# riffleBoost.net
KiCad netlist of a schematic drawn in EAGLE
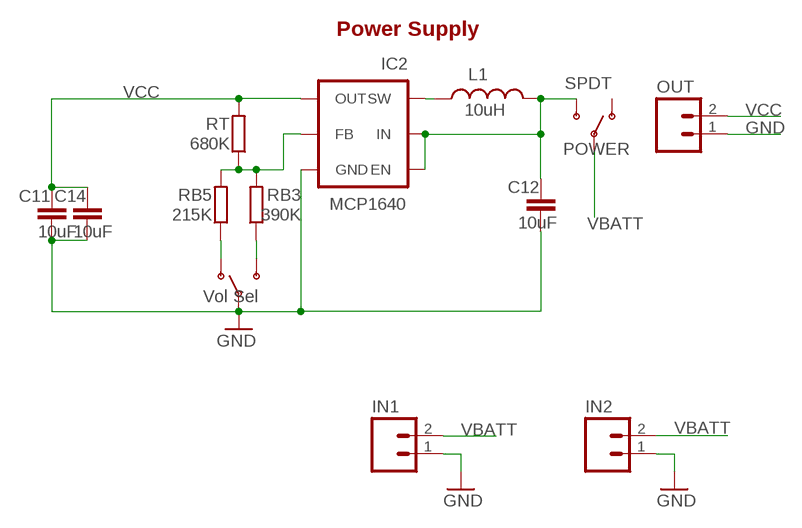
[diagram p0: schematic, sheet 1]

(export (version "E")
  (design (tool "Eeschema 10.0.6"))
  (components
    (comp (ref "C11")
      (value "10uF")
      (footprint "eagle-import:C0805")
      (libsource (lib "eagle-import") (part "C-EUC0805"))
    )
    (comp (ref "C12")
      (value "10uF")
      (footprint "eagle-import:C0805")
      (libsource (lib "eagle-import") (part "C-EUC0805"))
    )
    (comp (ref "C14")
      (value "10uF")
      (footprint "eagle-import:C0805")
      (libsource (lib "eagle-import") (part "C-EUC0805"))
    )
    (comp (ref "IC2")
      (value "MCP1640")
      (footprint "eagle-import:TSOT23-6")
      (libsource (lib "eagle-import") (part "MCP1640"))
    )
    (comp (ref "IN1")
      (value "M02PTH")
      (footprint "eagle-import:1X02")
      (libsource (lib "eagle-import") (part "M02PTH"))
    )
    (comp (ref "IN2")
      (value "M02-JST-2MM-SMT")
      (footprint "eagle-import:JST-2-SMD")
      (libsource (lib "eagle-import") (part "M02-JST-2MM-SMT"))
    )
    (comp (ref "L1")
      (value "10uH")
      (footprint "eagle-import:INDUCTOR_D30")
      (libsource (lib "eagle-import") (part "INDUCTOR_SMDD30"))
    )
    (comp (ref "OUT")
      (value "M021X02_NO_SILK")
      (footprint "eagle-import:1X02_NO_SILK")
      (libsource (lib "eagle-import") (part "M021X02_NO_SILK"))
    )
    (comp (ref "POWER")
      (value "SPDT")
      (footprint "eagle-import:SWITCH-SPDT-SMD")
      (libsource (lib "eagle-import") (part "SWITCH-SPSTSMD2"))
    )
    (comp (ref "RB3")
      (value "390K")
      (footprint "eagle-import:R0805")
      (libsource (lib "eagle-import") (part "R-EU_R0805"))
    )
    (comp (ref "RB5")
      (value "215K")
      (footprint "eagle-import:R0805")
      (libsource (lib "eagle-import") (part "R-EU_R0805"))
    )
    (comp (ref "RT")
      (value "680K")
      (footprint "eagle-import:R0805")
      (libsource (lib "eagle-import") (part "R-EU_R0805"))
    )
    (comp (ref "VOL1")
      (value "Vol Sel")
      (footprint "eagle-import:SWITCH-SPDT-SMD")
      (libsource (lib "eagle-import") (part "SWITCH-SPSTSMD2"))
    )
  )
  (nets
    (net (code "1") (name "/VBATT") (class "Default")
      (node (ref "IN1") (pin "2") (pinfunction "2_2") (pintype "passive"))
      (node (ref "IN2") (pin "2") (pinfunction "2_2") (pintype "passive"))
      (node (ref "POWER") (pin "2") (pinfunction "P_2") (pintype "passive"))
    )
    (net (code "2") (name "/VCC") (class "Default")
      (node (ref "C11") (pin "1") (pinfunction "1_1") (pintype "passive"))
      (node (ref "C14") (pin "1") (pinfunction "1_1") (pintype "passive"))
      (node (ref "IC2") (pin "5") (pinfunction "OUT_5") (pintype "passive"))
      (node (ref "OUT") (pin "2") (pinfunction "2_2") (pintype "passive"))
      (node (ref "RT") (pin "2") (pinfunction "2_2") (pintype "passive"))
    )
    (net (code "3") (name "GND") (class "Default")
      (node (ref "C11") (pin "2") (pinfunction "2_2") (pintype "passive"))
      (node (ref "C12") (pin "2") (pinfunction "2_2") (pintype "passive"))
      (node (ref "C14") (pin "2") (pinfunction "2_2") (pintype "passive"))
      (node (ref "IC2") (pin "2") (pinfunction "GND_2") (pintype "input"))
      (node (ref "IN1") (pin "1") (pinfunction "1_1") (pintype "passive"))
      (node (ref "IN2") (pin "1") (pinfunction "1_1") (pintype "passive"))
      (node (ref "OUT") (pin "1") (pinfunction "1_1") (pintype "passive"))
      (node (ref "VOL1") (pin "2") (pinfunction "P_2") (pintype "passive"))
    )
    (net (code "4") (name "Net-(IC2-EN)") (class "Default")
      (node (ref "C12") (pin "1") (pinfunction "1_1") (pintype "passive"))
      (node (ref "IC2") (pin "3") (pinfunction "EN_3") (pintype "input"))
      (node (ref "IC2") (pin "6") (pinfunction "IN_6") (pintype "input"))
      (node (ref "L1") (pin "P$1") (pinfunction "1_P$1") (pintype "passive"))
      (node (ref "POWER") (pin "3") (pinfunction "S_3") (pintype "passive"))
    )
    (net (code "5") (name "Net-(IC2-FB)") (class "Default")
      (node (ref "IC2") (pin "4") (pinfunction "FB_4") (pintype "input"))
      (node (ref "RB3") (pin "2") (pinfunction "2_2") (pintype "passive"))
      (node (ref "RB5") (pin "2") (pinfunction "2_2") (pintype "passive"))
      (node (ref "RT") (pin "1") (pinfunction "1_1") (pintype "passive"))
    )
    (net (code "6") (name "Net-(IC2-SW)") (class "Default")
      (node (ref "IC2") (pin "1") (pinfunction "SW_1") (pintype "output"))
      (node (ref "L1") (pin "P$2") (pinfunction "2_P$2") (pintype "passive"))
    )
    (net (code "7") (name "Net-(VOL1-O)") (class "Default")
      (node (ref "RB5") (pin "1") (pinfunction "1_1") (pintype "passive"))
      (node (ref "VOL1") (pin "1") (pinfunction "O_1") (pintype "passive"))
    )
    (net (code "8") (name "Net-(VOL1-S)") (class "Default")
      (node (ref "RB3") (pin "1") (pinfunction "1_1") (pintype "passive"))
      (node (ref "VOL1") (pin "3") (pinfunction "S_3") (pintype "passive"))
    )
    (net (code "9") (name "unconnected-(POWER-O-Pad1)") (class "Default")
      (node (ref "POWER") (pin "1") (pinfunction "O_1") (pintype "passive"))
    )
  )
)
